# Power.net
KiCad netlist of a schematic drawn in Altium Designer
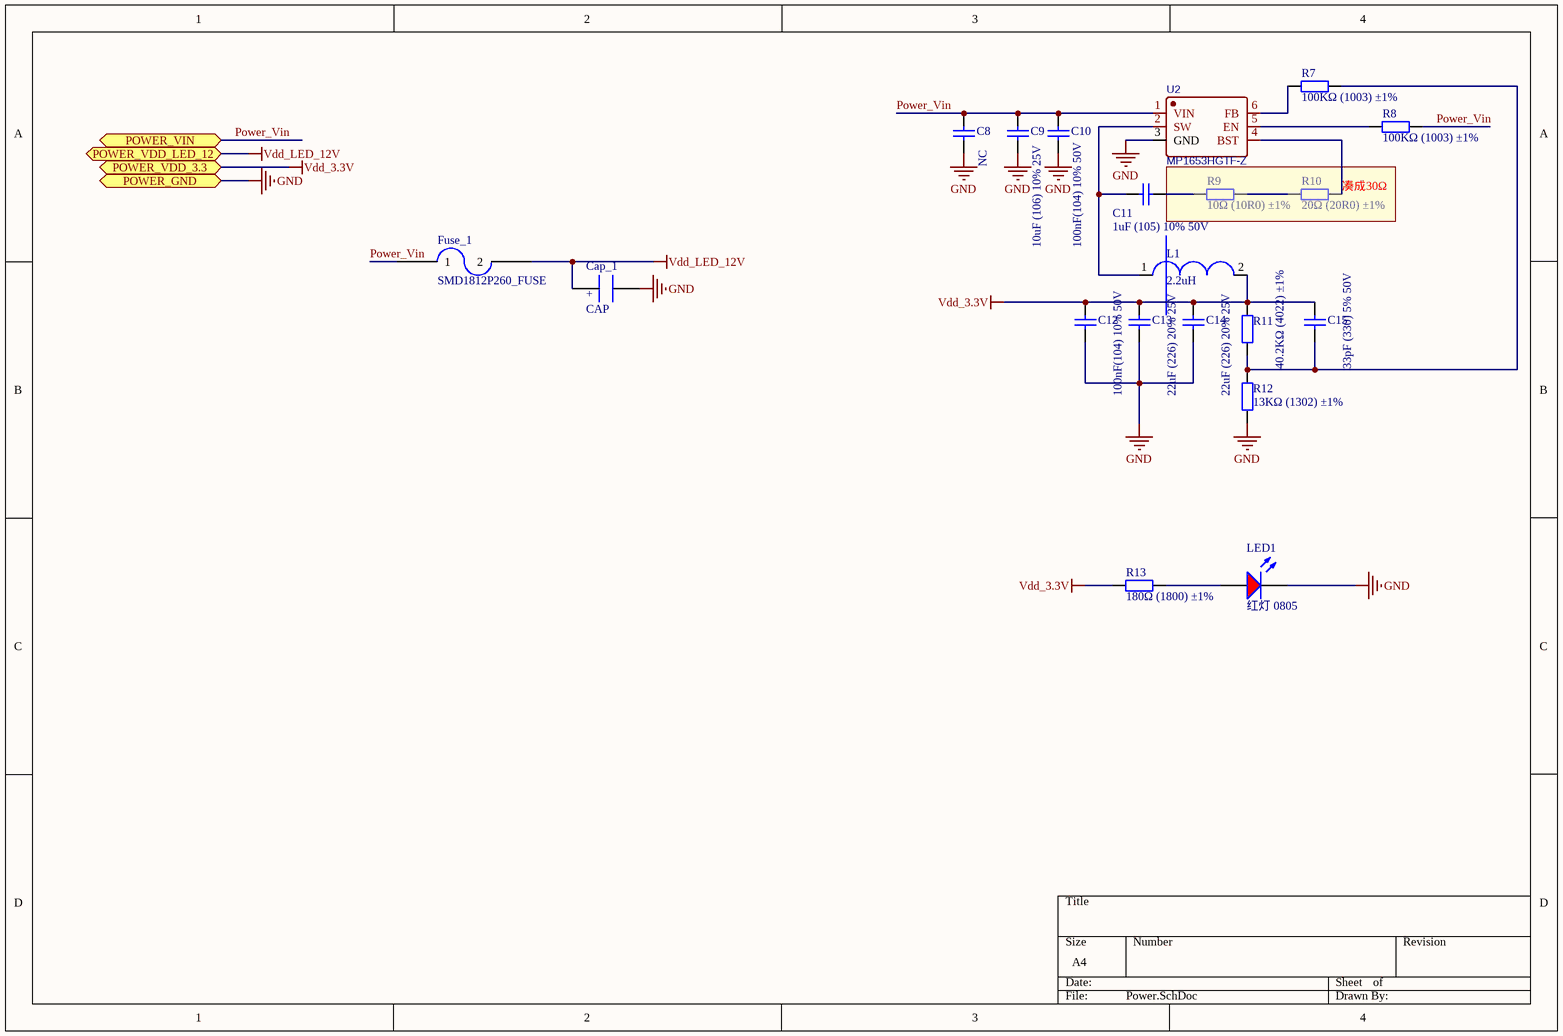
[diagram p0: Power.SchDoc]

(export (version "E")
  (design (tool "Eeschema 10.0.6"))
  (components
    (comp (ref "C8")
      (value "NC")
      (footprint "0805_C")
      (description "贴片电容")
      (libsource (lib "Miscellaneous Devices LC") (part "0805 10uF (106) 10% 25V"))
    )
    (comp (ref "C9")
      (value "10uF (106) 10% 25V")
      (footprint "0805_C")
      (description "贴片电容")
      (libsource (lib "Miscellaneous Devices LC") (part "0805 10uF (106) 10% 25V"))
    )
    (comp (ref "C10")
      (value "100nF(104) 10% 50V")
      (footprint "0805_C")
      (description "贴片电容")
      (libsource (lib "Miscellaneous Devices LC") (part "0805 100nF(104) 10% 50V"))
    )
    (comp (ref "C11")
      (value "1uF (105) 10% 50V")
      (footprint "0805_C")
      (description "贴片电容")
      (libsource (lib "Miscellaneous Devices LC") (part "0805 1uF (105) 10% 50V"))
    )
    (comp (ref "C12")
      (value "100nF(104) 10% 50V")
      (footprint "0805_C")
      (description "贴片电容")
      (libsource (lib "Miscellaneous Devices LC") (part "0805 100nF(104) 10% 50V"))
    )
    (comp (ref "C13")
      (value "22uF (226) 20% 25V")
      (footprint "0805_C")
      (description "贴片电容")
      (libsource (lib "Miscellaneous Devices LC") (part "0805 22uF (226) 20% 25V"))
    )
    (comp (ref "C14")
      (value "22uF (226) 20% 25V")
      (footprint "0805_C")
      (description "贴片电容")
      (libsource (lib "Miscellaneous Devices LC") (part "0805 22uF (226) 20% 25V"))
    )
    (comp (ref "C15")
      (value "33pF (330) 5% 50V")
      (footprint "0805_C")
      (description "贴片电容")
      (libsource (lib "Miscellaneous Devices LC") (part "0805 33pF (330) 5% 50V"))
    )
    (comp (ref "Cap_1") (value "CAP") (footprint "8X12_CAP") (libsource (lib "mylib") (part "CAP")))
    (comp (ref "Fuse_1")
      (value "SMD1812P260_FUSE")
      (footprint "SMD1812P260")
      (libsource (lib "mylib") (part "SMD1812P260_FUSE"))
    )
    (comp (ref "L1") (value "2.2uH") (footprint "L_4030") (libsource (lib "mylib") (part "33uH")))
    (comp (ref "LED1")
      (value "红灯 0805")
      (footprint "0805_LED_S1")
      (description "发光二极管")
      (libsource (lib "Miscellaneous Devices LC") (part "0805 红灯"))
    )
    (comp (ref "R7")
      (value "100KΩ (1003) ±1%")
      (footprint "0805_R")
      (description "贴片电阻")
      (libsource (lib "Miscellaneous Devices LC") (part "0805 100KΩ (1003) 1%"))
    )
    (comp (ref "R8")
      (value "100KΩ (1003) ±1%")
      (footprint "0805_R")
      (description "贴片电阻")
      (libsource (lib "Miscellaneous Devices LC") (part "0805 100KΩ (1003) 1%"))
    )
    (comp (ref "R9")
      (value "10Ω (10R0) ±1%")
      (footprint "0805_R")
      (description "贴片电阻")
      (libsource (lib "Miscellaneous Devices LC") (part "0805 10Ω (10R0) 1%"))
    )
    (comp (ref "R10")
      (value "20Ω (20R0) ±1%")
      (footprint "0805_R")
      (description "贴片电阻")
      (libsource (lib "Miscellaneous Devices LC") (part "0805 20Ω (20R0) 1%"))
    )
    (comp (ref "R11")
      (value "40.2KΩ (4022) ±1%")
      (footprint "0805_R")
      (description "贴片电阻")
      (libsource (lib "Miscellaneous Devices LC") (part "0805 40.2KΩ (4022) 1%"))
    )
    (comp (ref "R12")
      (value "13KΩ (1302) ±1%")
      (footprint "0805_R")
      (description "贴片电阻")
      (libsource (lib "Miscellaneous Devices LC") (part "0805 13KΩ (1302) 1%"))
    )
    (comp (ref "R13")
      (value "180Ω (1800) ±1%")
      (footprint "0805_R")
      (description "贴片电阻")
      (libsource (lib "Miscellaneous Devices LC") (part "0805 180Ω (1800) 1%"))
    )
    (comp (ref "U2")
      (value "MP1653HGTF-Z")
      (footprint "SOT563-6")
      (fields (field (name "BOM_SUPPLIER PART") "C132613"))
      (libsource (lib "mylib") (part "MP1653HGTF-Z"))
    )
  )
  (nets
    (net (code "1") (name "/Power_Vin") (class "Default")
      (node (ref "C10") (pin "2") (pinfunction "2_2") (pintype "passive"))
      (node (ref "C8") (pin "2") (pinfunction "2_2") (pintype "passive"))
      (node (ref "C9") (pin "2") (pinfunction "2_2") (pintype "passive"))
      (node (ref "Fuse_1") (pin "1") (pinfunction "1_1") (pintype "passive"))
      (node (ref "R8") (pin "2") (pinfunction "2_2") (pintype "passive"))
      (node (ref "U2") (pin "1") (pinfunction "VIN_1") (pintype "passive"))
    )
    (net (code "2") (name "GND") (class "Default")
      (node (ref "C10") (pin "1") (pinfunction "1_1") (pintype "passive"))
      (node (ref "C12") (pin "1") (pinfunction "1_1") (pintype "passive"))
      (node (ref "C13") (pin "1") (pinfunction "1_1") (pintype "passive"))
      (node (ref "C14") (pin "1") (pinfunction "1_1") (pintype "passive"))
      (node (ref "C8") (pin "1") (pinfunction "1_1") (pintype "passive"))
      (node (ref "C9") (pin "1") (pinfunction "1_1") (pintype "passive"))
      (node (ref "Cap_1") (pin "2") (pinfunction "2_2") (pintype "passive"))
      (node (ref "LED1") (pin "K") (pinfunction "K_K") (pintype "passive"))
      (node (ref "R12") (pin "1") (pinfunction "1_1") (pintype "passive"))
      (node (ref "U2") (pin "3") (pinfunction "GND_3") (pintype "passive"))
    )
    (net (code "3") (name "Net-(C11-Pad1)") (class "Default")
      (node (ref "C11") (pin "1") (pinfunction "1_1") (pintype "passive"))
      (node (ref "R9") (pin "2") (pinfunction "2_2") (pintype "passive"))
    )
    (net (code "4") (name "Net-(C15-Pad1)") (class "Default")
      (node (ref "C15") (pin "1") (pinfunction "1_1") (pintype "passive"))
      (node (ref "R11") (pin "2") (pinfunction "2_2") (pintype "passive"))
      (node (ref "R12") (pin "2") (pinfunction "2_2") (pintype "passive"))
      (node (ref "R7") (pin "2") (pinfunction "2_2") (pintype "passive"))
    )
    (net (code "5") (name "Net-(LED1-PadA)") (class "Default")
      (node (ref "LED1") (pin "A") (pinfunction "A_A") (pintype "passive"))
      (node (ref "R13") (pin "2") (pinfunction "2_2") (pintype "passive"))
    )
    (net (code "6") (name "Net-(R10-Pad2)") (class "Default")
      (node (ref "R10") (pin "2") (pinfunction "2_2") (pintype "passive"))
      (node (ref "R9") (pin "1") (pinfunction "1_1") (pintype "passive"))
    )
    (net (code "7") (name "Net-(U2-BST)") (class "Default")
      (node (ref "R10") (pin "1") (pinfunction "1_1") (pintype "passive"))
      (node (ref "U2") (pin "4") (pinfunction "BST_4") (pintype "passive"))
    )
    (net (code "8") (name "Net-(U2-EN)") (class "Default")
      (node (ref "R8") (pin "1") (pinfunction "1_1") (pintype "passive"))
      (node (ref "U2") (pin "5") (pinfunction "EN_5") (pintype "passive"))
    )
    (net (code "9") (name "Net-(U2-FB)") (class "Default")
      (node (ref "R7") (pin "1") (pinfunction "1_1") (pintype "passive"))
      (node (ref "U2") (pin "6") (pinfunction "FB_6") (pintype "passive"))
    )
    (net (code "10") (name "Net-(U2-SW)") (class "Default")
      (node (ref "C11") (pin "2") (pinfunction "2_2") (pintype "passive"))
      (node (ref "L1") (pin "1") (pinfunction "1_1") (pintype "passive"))
      (node (ref "U2") (pin "2") (pinfunction "SW_2") (pintype "passive"))
    )
    (net (code "11") (name "Vdd_3.3V") (class "Default")
      (node (ref "C12") (pin "2") (pinfunction "2_2") (pintype "passive"))
      (node (ref "C13") (pin "2") (pinfunction "2_2") (pintype "passive"))
      (node (ref "C14") (pin "2") (pinfunction "2_2") (pintype "passive"))
      (node (ref "C15") (pin "2") (pinfunction "2_2") (pintype "passive"))
      (node (ref "L1") (pin "2") (pinfunction "2_2") (pintype "passive"))
      (node (ref "R11") (pin "1") (pinfunction "1_1") (pintype "passive"))
      (node (ref "R13") (pin "1") (pinfunction "1_1") (pintype "passive"))
    )
    (net (code "12") (name "Vdd_LED_12V") (class "Default")
      (node (ref "Cap_1") (pin "1") (pinfunction "1_1") (pintype "passive"))
      (node (ref "Fuse_1") (pin "2") (pinfunction "2_2") (pintype "passive"))
    )
  )
)
